# Buck_Converter_5V.net
KiCad netlist of a schematic drawn in Altium Designer
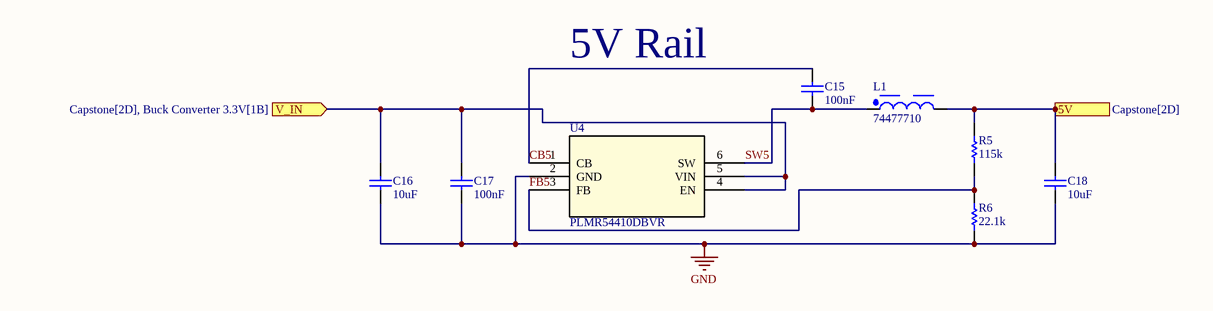
[diagram p0: Buck Converter 5V.SchDoc]

(export (version "E")
  (design (tool "Eeschema 10.0.6"))
  (components
    (comp (ref "C15")
      (value "100nF")
      (footprint "CAPC2013X135X45LL10T25")
      (description "Chip Capacitor, 4.7 uF, +/- 10%, 16 V, -55 to 85 degC, 0805 (2012 Metric), RoHS, Tape and Reel")
      (fields (field (name "TOLERANCE") "10%") (field (name "PARTNUMBER") "GRM21BR61C475KA88L"))
      (libsource (lib "Altium Content Vault") (part "CAP-NP-2"))
    )
    (comp (ref "C16")
      (value "10uF")
      (footprint "CAPC2013X135X45LL10T25")
      (description "Chip Capacitor, 4.7 uF, +/- 10%, 16 V, -55 to 85 degC, 0805 (2012 Metric), RoHS, Tape and Reel")
      (fields (field (name "TOLERANCE") "10%") (field (name "PARTNUMBER") "GRM21BR61C475KA88L"))
      (libsource (lib "Altium Content Vault") (part "CAP-NP-2"))
    )
    (comp (ref "C17")
      (value "100nF")
      (footprint "CAPC2013X135X45LL10T25")
      (description "Chip Capacitor, 4.7 uF, +/- 10%, 16 V, -55 to 85 degC, 0805 (2012 Metric), RoHS, Tape and Reel")
      (fields (field (name "TOLERANCE") "10%") (field (name "PARTNUMBER") "GRM21BR61C475KA88L"))
      (libsource (lib "Altium Content Vault") (part "CAP-NP-2"))
    )
    (comp (ref "C18")
      (value "10uF")
      (footprint "CAPC2013X135X45LL10T25")
      (description "Chip Capacitor, 4.7 uF, +/- 10%, 16 V, -55 to 85 degC, 0805 (2012 Metric), RoHS, Tape and Reel")
      (fields (field (name "TOLERANCE") "10%") (field (name "PARTNUMBER") "GRM21BR61C475KA88L"))
      (libsource (lib "Altium Content Vault") (part "CAP-NP-2"))
    )
    (comp (ref "L1")
      (value "74477710")
      (footprint "WE-PD_7345")
      (fields (field (name "TOLERANCE") "20%"))
      (libsource (lib "Altium Content Vault") (part "Inductor - 2"))
    )
    (comp (ref "R5")
      (value "115k")
      (footprint "RESC1608X55X25ML10T15")
      (description "Chip Resistor, 0 Ohm, +/- 5%, 0.1 W, -55 to 155 degC, 0603 (1608 Metric), RoHS, Tape and Reel")
      (fields (field (name "TOLERANCE") "5%") (field (name "MANUFACTURER") "Yageo"))
      (libsource (lib "Altium Content Vault") (part "RES-2"))
    )
    (comp (ref "R6")
      (value "22.1k")
      (footprint "RESC1608X55X25ML10T15")
      (description "Chip Resistor, 0 Ohm, +/- 5%, 0.1 W, -55 to 155 degC, 0603 (1608 Metric), RoHS, Tape and Reel")
      (fields (field (name "TOLERANCE") "5%") (field (name "MANUFACTURER") "Yageo"))
      (libsource (lib "Altium Content Vault") (part "RES-2"))
    )
    (comp (ref "U4")
      (value "PLMR54410DBVR")
      (footprint "U_SOT-23_TEX")
      (description "No Description Available")
      (libsource (lib "PLMR54410DBVR") (part "PLMR54410DBVR"))
    )
  )
  (nets
    (net (code "1") (name "/5V") (class "Default")
      (node (ref "C18") (pin "2") (pinfunction "2_2") (pintype "passive"))
      (node (ref "L1") (pin "2") (pinfunction "2_2") (pintype "passive"))
      (node (ref "R5") (pin "2") (pinfunction "2_2") (pintype "passive"))
    )
    (net (code "2") (name "/CB5") (class "Default")
      (node (ref "C15") (pin "2") (pinfunction "2_2") (pintype "passive"))
      (node (ref "U4") (pin "1") (pinfunction "CB_1") (pintype "power_in"))
    )
    (net (code "3") (name "/FB5") (class "Default")
      (node (ref "R5") (pin "1") (pinfunction "1_1") (pintype "passive"))
      (node (ref "R6") (pin "2") (pinfunction "2_2") (pintype "passive"))
      (node (ref "U4") (pin "3") (pinfunction "FB_3") (pintype "passive"))
    )
    (net (code "4") (name "/SW5") (class "Default")
      (node (ref "C15") (pin "1") (pinfunction "1_1") (pintype "passive"))
      (node (ref "L1") (pin "1") (pinfunction "1_1") (pintype "passive"))
      (node (ref "U4") (pin "6") (pinfunction "SW_6") (pintype "power_in"))
    )
    (net (code "5") (name "/V_IN") (class "Default")
      (node (ref "C16") (pin "2") (pinfunction "2_2") (pintype "passive"))
      (node (ref "C17") (pin "2") (pinfunction "2_2") (pintype "passive"))
      (node (ref "U4") (pin "4") (pinfunction "EN_4") (pintype "passive"))
      (node (ref "U4") (pin "5") (pinfunction "VIN_5") (pintype "passive"))
    )
    (net (code "6") (name "GND") (class "Default")
      (node (ref "C16") (pin "1") (pinfunction "1_1") (pintype "passive"))
      (node (ref "C17") (pin "1") (pinfunction "1_1") (pintype "passive"))
      (node (ref "C18") (pin "1") (pinfunction "1_1") (pintype "passive"))
      (node (ref "R6") (pin "1") (pinfunction "1_1") (pintype "passive"))
      (node (ref "U4") (pin "2") (pinfunction "GND_2") (pintype "passive"))
    )
  )
)
